# io-a-1.net
KiCad netlist of a schematic drawn in EAGLE
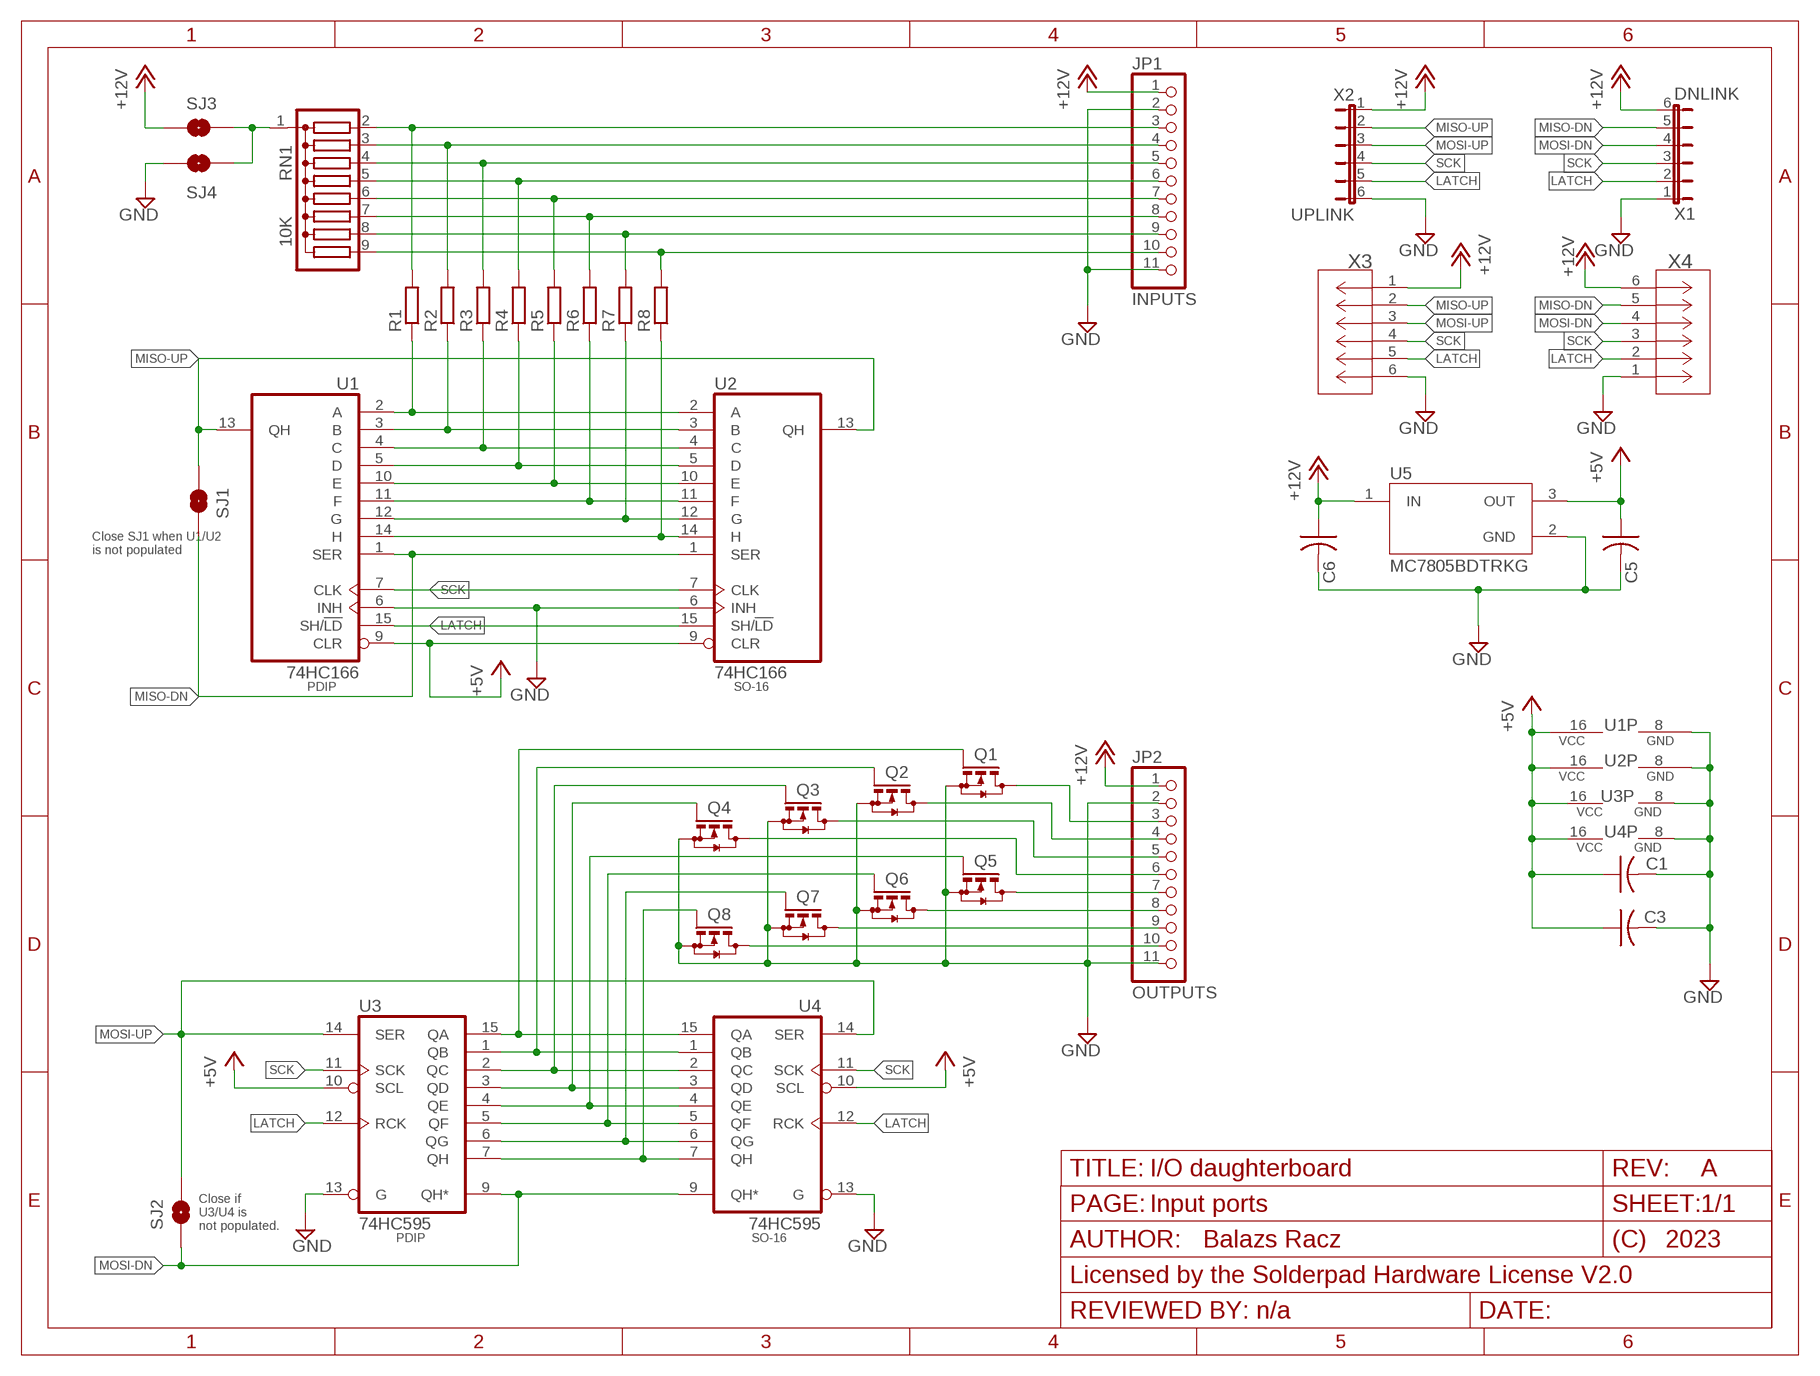
[diagram p0: schematic, sheet 1]

(export (version "E")
  (design (tool "Eeschema 10.0.6"))
  (components
    (comp (ref "C1")
      (value "C-USC0805")
      (footprint "eagle-import:C0805")
      (libsource (lib "eagle-import") (part "C-USC0805"))
    )
    (comp (ref "C3")
      (value "C-USC0805")
      (footprint "eagle-import:C0805")
      (libsource (lib "eagle-import") (part "C-USC0805"))
    )
    (comp (ref "C5")
      (value "C-USC0805")
      (footprint "eagle-import:C0805")
      (libsource (lib "eagle-import") (part "C-USC0805"))
    )
    (comp (ref "C6")
      (value "C-USC0805")
      (footprint "eagle-import:C0805")
      (libsource (lib "eagle-import") (part "C-USC0805"))
    )
    (comp (ref "JP1")
      (value "INPUTS")
      (footprint "eagle-import:1X11")
      (libsource (lib "eagle-import") (part "PINHD-1X11"))
    )
    (comp (ref "JP2")
      (value "OUTPUTS")
      (footprint "eagle-import:1X11")
      (libsource (lib "eagle-import") (part "PINHD-1X11"))
    )
    (comp (ref "Q1")
      (value "BSS123")
      (footprint "eagle-import:SOT23")
      (libsource (lib "eagle-import") (part "BSS123"))
    )
    (comp (ref "Q2")
      (value "BSS123")
      (footprint "eagle-import:SOT23")
      (libsource (lib "eagle-import") (part "BSS123"))
    )
    (comp (ref "Q3")
      (value "BSS123")
      (footprint "eagle-import:SOT23")
      (libsource (lib "eagle-import") (part "BSS123"))
    )
    (comp (ref "Q4")
      (value "BSS123")
      (footprint "eagle-import:SOT23")
      (libsource (lib "eagle-import") (part "BSS123"))
    )
    (comp (ref "Q5")
      (value "BSS123")
      (footprint "eagle-import:SOT23")
      (libsource (lib "eagle-import") (part "BSS123"))
    )
    (comp (ref "Q6")
      (value "BSS123")
      (footprint "eagle-import:SOT23")
      (libsource (lib "eagle-import") (part "BSS123"))
    )
    (comp (ref "Q7")
      (value "BSS123")
      (footprint "eagle-import:SOT23")
      (libsource (lib "eagle-import") (part "BSS123"))
    )
    (comp (ref "Q8")
      (value "BSS123")
      (footprint "eagle-import:SOT23")
      (libsource (lib "eagle-import") (part "BSS123"))
    )
    (comp (ref "R1")
      (value "R-EU_R0805")
      (footprint "eagle-import:R0805")
      (libsource (lib "eagle-import") (part "R-EU_R0805"))
    )
    (comp (ref "R2")
      (value "R-EU_R0805")
      (footprint "eagle-import:R0805")
      (libsource (lib "eagle-import") (part "R-EU_R0805"))
    )
    (comp (ref "R3")
      (value "R-EU_R0805")
      (footprint "eagle-import:R0805")
      (libsource (lib "eagle-import") (part "R-EU_R0805"))
    )
    (comp (ref "R4")
      (value "R-EU_R0805")
      (footprint "eagle-import:R0805")
      (libsource (lib "eagle-import") (part "R-EU_R0805"))
    )
    (comp (ref "R5")
      (value "R-EU_R0805")
      (footprint "eagle-import:R0805")
      (libsource (lib "eagle-import") (part "R-EU_R0805"))
    )
    (comp (ref "R6")
      (value "R-EU_R0805")
      (footprint "eagle-import:R0805")
      (libsource (lib "eagle-import") (part "R-EU_R0805"))
    )
    (comp (ref "R7")
      (value "R-EU_R0805")
      (footprint "eagle-import:R0805")
      (libsource (lib "eagle-import") (part "R-EU_R0805"))
    )
    (comp (ref "R8")
      (value "R-EU_R0805")
      (footprint "eagle-import:R0805")
      (libsource (lib "eagle-import") (part "R-EU_R0805"))
    )
    (comp (ref "RN1")
      (value "10K")
      (footprint "eagle-import:SIL9")
      (libsource (lib "eagle-import") (part "G08R"))
    )
    (comp (ref "SJ1")
      (value "SJRND2")
      (footprint "eagle-import:SJ_RND2")
      (libsource (lib "eagle-import") (part "SJRND2"))
    )
    (comp (ref "SJ2")
      (value "SJRND2")
      (footprint "eagle-import:SJ_RND2")
      (libsource (lib "eagle-import") (part "SJRND2"))
    )
    (comp (ref "SJ3")
      (value "SJRND2")
      (footprint "eagle-import:SJ_RND2")
      (libsource (lib "eagle-import") (part "SJRND2"))
    )
    (comp (ref "SJ4")
      (value "SJRND2")
      (footprint "eagle-import:SJ_RND2")
      (libsource (lib "eagle-import") (part "SJRND2"))
    )
    (comp (ref "U1")
      (value "74HC166")
      (footprint "eagle-import:DIL16")
      (libsource (lib "eagle-import") (part "74166N"))
    )
    (comp (ref "U2")
      (value "74HC166")
      (footprint "eagle-import:SO16")
      (libsource (lib "eagle-import") (part "74166D"))
    )
    (comp (ref "U3")
      (value "74HC595")
      (footprint "eagle-import:DIL16")
      (libsource (lib "eagle-import") (part "74595NHCT"))
    )
    (comp (ref "U4")
      (value "74HC595")
      (footprint "eagle-import:SO16")
      (libsource (lib "eagle-import") (part "74595DHCT"))
    )
    (comp (ref "U5")
      (value "MC7805BDTRKG")
      (footprint "eagle-import:DPAK229P990X238-4N")
      (fields (field (name "MANUFACTURER") "ON Semiconductor"))
      (libsource (lib "eagle-import") (part "MC7805BDTRKG"))
    )
    (comp (ref "X1")
      (value "DNLINK")
      (footprint "eagle-import:JP6F")
      (libsource (lib "eagle-import") (part "JP6-FLAT"))
    )
    (comp (ref "X2")
      (value "UPLINK")
      (footprint "eagle-import:JP6F-FEM")
      (libsource (lib "eagle-import") (part "JP6-FLATFEMALE"))
    )
    (comp (ref "X3")
      (value "MOLEX_530470610CON_530470610_MOL")
      (footprint "eagle-import:CON_530470610_MOL")
      (fields
        (field (name "MANUFACTURER_PART_NUMBER") "530470610")
        (field (name "COPYRIGHT") "Copyright (C) 2023 Ultra Librarian. All rights reserved.")
      )
      (libsource (lib "eagle-import") (part "MOLEX_530470610CON_530470610_MOL"))
    )
    (comp (ref "X4")
      (value "MOLEX_530470610CON_530470610_MOL")
      (footprint "eagle-import:CON_530470610_MOL")
      (fields
        (field (name "MANUFACTURER_PART_NUMBER") "530470610")
        (field (name "COPYRIGHT") "Copyright (C) 2023 Ultra Librarian. All rights reserved.")
      )
      (libsource (lib "eagle-import") (part "MOLEX_530470610CON_530470610_MOL"))
    )
  )
  (nets
    (net (code "1") (name "+5V") (class "Default")
      (node (ref "C1") (pin "1") (pinfunction "1_1") (pintype "passive"))
      (node (ref "C3") (pin "1") (pinfunction "1_1") (pintype "passive"))
      (node (ref "C5") (pin "1") (pinfunction "1_1") (pintype "passive"))
      (node (ref "U1") (pin "16") (pinfunction "VCC_16") (pintype "power_in"))
      (node (ref "U1") (pin "9") (pinfunction "CLR_9") (pintype "input"))
      (node (ref "U2") (pin "16") (pinfunction "VCC_16") (pintype "power_in"))
      (node (ref "U2") (pin "9") (pinfunction "CLR_9") (pintype "input"))
      (node (ref "U3") (pin "10") (pinfunction "SCL_10") (pintype "input"))
      (node (ref "U3") (pin "16") (pinfunction "VCC_16") (pintype "power_in"))
      (node (ref "U4") (pin "10") (pinfunction "SCL_10") (pintype "input"))
      (node (ref "U4") (pin "16") (pinfunction "VCC_16") (pintype "power_in"))
      (node (ref "U5") (pin "3") (pinfunction "OUT_3") (pintype "output"))
    )
    (net (code "2") (name "+12V") (class "Default")
      (node (ref "C6") (pin "1") (pinfunction "1_1") (pintype "passive"))
      (node (ref "JP1") (pin "1") (pinfunction "1_1") (pintype "passive"))
      (node (ref "JP2") (pin "1") (pinfunction "1_1") (pintype "passive"))
      (node (ref "SJ3") (pin "P$2") (pinfunction "2_P$2") (pintype "passive"))
      (node (ref "U5") (pin "1") (pinfunction "IN_1") (pintype "input"))
      (node (ref "X1") (pin "6") (pinfunction "6_6") (pintype "passive"))
      (node (ref "X2") (pin "1") (pinfunction "1_1") (pintype "passive"))
      (node (ref "X3") (pin "1") (pinfunction "1_1") (pintype "passive"))
      (node (ref "X4") (pin "6") (pinfunction "6_6") (pintype "passive"))
    )
    (net (code "3") (name "GND") (class "Default")
      (node (ref "C1") (pin "2") (pinfunction "2_2") (pintype "passive"))
      (node (ref "C3") (pin "2") (pinfunction "2_2") (pintype "passive"))
      (node (ref "C5") (pin "2") (pinfunction "2_2") (pintype "passive"))
      (node (ref "C6") (pin "2") (pinfunction "2_2") (pintype "passive"))
      (node (ref "JP1") (pin "11") (pinfunction "11_11") (pintype "passive"))
      (node (ref "JP1") (pin "2") (pinfunction "2_2") (pintype "passive"))
      (node (ref "JP2") (pin "11") (pinfunction "11_11") (pintype "passive"))
      (node (ref "JP2") (pin "2") (pinfunction "2_2") (pintype "passive"))
      (node (ref "Q1") (pin "2") (pinfunction "S_2") (pintype "passive"))
      (node (ref "Q2") (pin "2") (pinfunction "S_2") (pintype "passive"))
      (node (ref "Q3") (pin "2") (pinfunction "S_2") (pintype "passive"))
      (node (ref "Q4") (pin "2") (pinfunction "S_2") (pintype "passive"))
      (node (ref "Q5") (pin "2") (pinfunction "S_2") (pintype "passive"))
      (node (ref "Q6") (pin "2") (pinfunction "S_2") (pintype "passive"))
      (node (ref "Q7") (pin "2") (pinfunction "S_2") (pintype "passive"))
      (node (ref "Q8") (pin "2") (pinfunction "S_2") (pintype "passive"))
      (node (ref "SJ4") (pin "P$2") (pinfunction "2_P$2") (pintype "passive"))
      (node (ref "U1") (pin "6") (pinfunction "INH_6") (pintype "input"))
      (node (ref "U1") (pin "8") (pinfunction "GND_8") (pintype "power_in"))
      (node (ref "U2") (pin "6") (pinfunction "INH_6") (pintype "input"))
      (node (ref "U2") (pin "8") (pinfunction "GND_8") (pintype "power_in"))
      (node (ref "U3") (pin "13") (pinfunction "G_13") (pintype "input"))
      (node (ref "U3") (pin "8") (pinfunction "GND_8") (pintype "power_in"))
      (node (ref "U4") (pin "13") (pinfunction "G_13") (pintype "input"))
      (node (ref "U4") (pin "8") (pinfunction "GND_8") (pintype "power_in"))
      (node (ref "U5") (pin "2") (pinfunction "GND_2") (pintype "power_in"))
      (node (ref "X1") (pin "1") (pinfunction "1_1") (pintype "passive"))
      (node (ref "X2") (pin "6") (pinfunction "6_6") (pintype "passive"))
      (node (ref "X3") (pin "6") (pinfunction "6_6") (pintype "passive"))
      (node (ref "X4") (pin "1") (pinfunction "1_1") (pintype "passive"))
    )
    (net (code "4") (name "LATCH") (class "Default")
      (node (ref "U1") (pin "15") (pinfunction "SH/~{LD}_15") (pintype "input"))
      (node (ref "U2") (pin "15") (pinfunction "SH/~{LD}_15") (pintype "input"))
      (node (ref "U3") (pin "12") (pinfunction "RCK_12") (pintype "input"))
      (node (ref "U4") (pin "12") (pinfunction "RCK_12") (pintype "input"))
      (node (ref "X1") (pin "2") (pinfunction "2_2") (pintype "passive"))
      (node (ref "X2") (pin "5") (pinfunction "5_5") (pintype "passive"))
      (node (ref "X3") (pin "5") (pinfunction "5_5") (pintype "passive"))
      (node (ref "X4") (pin "2") (pinfunction "2_2") (pintype "passive"))
    )
    (net (code "5") (name "MISO-DN") (class "Default")
      (node (ref "SJ1") (pin "P$1") (pinfunction "1_P$1") (pintype "passive"))
      (node (ref "U1") (pin "1") (pinfunction "SER_1") (pintype "input"))
      (node (ref "U2") (pin "1") (pinfunction "SER_1") (pintype "input"))
      (node (ref "X1") (pin "5") (pinfunction "5_5") (pintype "passive"))
      (node (ref "X4") (pin "5") (pinfunction "5_5") (pintype "passive"))
    )
    (net (code "6") (name "MISO-UP") (class "Default")
      (node (ref "SJ1") (pin "P$2") (pinfunction "2_P$2") (pintype "passive"))
      (node (ref "U1") (pin "13") (pinfunction "QH_13") (pintype "output"))
      (node (ref "U2") (pin "13") (pinfunction "QH_13") (pintype "output"))
      (node (ref "X2") (pin "2") (pinfunction "2_2") (pintype "passive"))
      (node (ref "X3") (pin "2") (pinfunction "2_2") (pintype "passive"))
    )
    (net (code "7") (name "MOSI-DN") (class "Default")
      (node (ref "SJ2") (pin "P$1") (pinfunction "1_P$1") (pintype "passive"))
      (node (ref "U3") (pin "9") (pinfunction "QH*_9") (pintype "tri_state"))
      (node (ref "U4") (pin "9") (pinfunction "QH*_9") (pintype "tri_state"))
      (node (ref "X1") (pin "4") (pinfunction "4_4") (pintype "passive"))
      (node (ref "X4") (pin "4") (pinfunction "4_4") (pintype "passive"))
    )
    (net (code "8") (name "MOSI-UP") (class "Default")
      (node (ref "SJ2") (pin "P$2") (pinfunction "2_P$2") (pintype "passive"))
      (node (ref "U3") (pin "14") (pinfunction "SER_14") (pintype "input"))
      (node (ref "U4") (pin "14") (pinfunction "SER_14") (pintype "input"))
      (node (ref "X2") (pin "3") (pinfunction "3_3") (pintype "passive"))
      (node (ref "X3") (pin "3") (pinfunction "3_3") (pintype "passive"))
    )
    (net (code "9") (name "Net-(JP1-Pad3)") (class "Default")
      (node (ref "JP1") (pin "3") (pinfunction "3_3") (pintype "passive"))
      (node (ref "R1") (pin "2") (pinfunction "2_2") (pintype "passive"))
      (node (ref "RN1") (pin "2") (pinfunction "2_2") (pintype "passive"))
    )
    (net (code "10") (name "Net-(JP1-Pad4)") (class "Default")
      (node (ref "JP1") (pin "4") (pinfunction "4_4") (pintype "passive"))
      (node (ref "R2") (pin "2") (pinfunction "2_2") (pintype "passive"))
      (node (ref "RN1") (pin "3") (pinfunction "3_3") (pintype "passive"))
    )
    (net (code "11") (name "Net-(JP1-Pad5)") (class "Default")
      (node (ref "JP1") (pin "5") (pinfunction "5_5") (pintype "passive"))
      (node (ref "R3") (pin "2") (pinfunction "2_2") (pintype "passive"))
      (node (ref "RN1") (pin "4") (pinfunction "4_4") (pintype "passive"))
    )
    (net (code "12") (name "Net-(JP1-Pad6)") (class "Default")
      (node (ref "JP1") (pin "6") (pinfunction "6_6") (pintype "passive"))
      (node (ref "R4") (pin "2") (pinfunction "2_2") (pintype "passive"))
      (node (ref "RN1") (pin "5") (pinfunction "5_5") (pintype "passive"))
    )
    (net (code "13") (name "Net-(JP1-Pad7)") (class "Default")
      (node (ref "JP1") (pin "7") (pinfunction "7_7") (pintype "passive"))
      (node (ref "R5") (pin "2") (pinfunction "2_2") (pintype "passive"))
      (node (ref "RN1") (pin "6") (pinfunction "6_6") (pintype "passive"))
    )
    (net (code "14") (name "Net-(JP1-Pad8)") (class "Default")
      (node (ref "JP1") (pin "8") (pinfunction "8_8") (pintype "passive"))
      (node (ref "R6") (pin "2") (pinfunction "2_2") (pintype "passive"))
      (node (ref "RN1") (pin "7") (pinfunction "7_7") (pintype "passive"))
    )
    (net (code "15") (name "Net-(JP1-Pad9)") (class "Default")
      (node (ref "JP1") (pin "9") (pinfunction "9_9") (pintype "passive"))
      (node (ref "R7") (pin "2") (pinfunction "2_2") (pintype "passive"))
      (node (ref "RN1") (pin "8") (pinfunction "8_8") (pintype "passive"))
    )
    (net (code "16") (name "Net-(JP1-Pad10)") (class "Default")
      (node (ref "JP1") (pin "10") (pinfunction "10_10") (pintype "passive"))
      (node (ref "R8") (pin "2") (pinfunction "2_2") (pintype "passive"))
      (node (ref "RN1") (pin "9") (pinfunction "9_9") (pintype "passive"))
    )
    (net (code "17") (name "Net-(Q1-D)") (class "Default")
      (node (ref "JP2") (pin "3") (pinfunction "3_3") (pintype "passive"))
      (node (ref "Q1") (pin "3") (pinfunction "D_3") (pintype "passive"))
    )
    (net (code "18") (name "Net-(Q1-G)") (class "Default")
      (node (ref "Q1") (pin "1") (pinfunction "G_1") (pintype "passive"))
      (node (ref "U3") (pin "15") (pinfunction "QA_15") (pintype "tri_state"))
      (node (ref "U4") (pin "15") (pinfunction "QA_15") (pintype "tri_state"))
    )
    (net (code "19") (name "Net-(Q2-D)") (class "Default")
      (node (ref "JP2") (pin "4") (pinfunction "4_4") (pintype "passive"))
      (node (ref "Q2") (pin "3") (pinfunction "D_3") (pintype "passive"))
    )
    (net (code "20") (name "Net-(Q2-G)") (class "Default")
      (node (ref "Q2") (pin "1") (pinfunction "G_1") (pintype "passive"))
      (node (ref "U3") (pin "1") (pinfunction "QB_1") (pintype "tri_state"))
      (node (ref "U4") (pin "1") (pinfunction "QB_1") (pintype "tri_state"))
    )
    (net (code "21") (name "Net-(Q3-D)") (class "Default")
      (node (ref "JP2") (pin "5") (pinfunction "5_5") (pintype "passive"))
      (node (ref "Q3") (pin "3") (pinfunction "D_3") (pintype "passive"))
    )
    (net (code "22") (name "Net-(Q3-G)") (class "Default")
      (node (ref "Q3") (pin "1") (pinfunction "G_1") (pintype "passive"))
      (node (ref "U3") (pin "2") (pinfunction "QC_2") (pintype "tri_state"))
      (node (ref "U4") (pin "2") (pinfunction "QC_2") (pintype "tri_state"))
    )
    (net (code "23") (name "Net-(Q4-D)") (class "Default")
      (node (ref "JP2") (pin "6") (pinfunction "6_6") (pintype "passive"))
      (node (ref "Q4") (pin "3") (pinfunction "D_3") (pintype "passive"))
    )
    (net (code "24") (name "Net-(Q4-G)") (class "Default")
      (node (ref "Q4") (pin "1") (pinfunction "G_1") (pintype "passive"))
      (node (ref "U3") (pin "3") (pinfunction "QD_3") (pintype "tri_state"))
      (node (ref "U4") (pin "3") (pinfunction "QD_3") (pintype "tri_state"))
    )
    (net (code "25") (name "Net-(Q5-D)") (class "Default")
      (node (ref "JP2") (pin "7") (pinfunction "7_7") (pintype "passive"))
      (node (ref "Q5") (pin "3") (pinfunction "D_3") (pintype "passive"))
    )
    (net (code "26") (name "Net-(Q5-G)") (class "Default")
      (node (ref "Q5") (pin "1") (pinfunction "G_1") (pintype "passive"))
      (node (ref "U3") (pin "4") (pinfunction "QE_4") (pintype "tri_state"))
      (node (ref "U4") (pin "4") (pinfunction "QE_4") (pintype "tri_state"))
    )
    (net (code "27") (name "Net-(Q6-D)") (class "Default")
      (node (ref "JP2") (pin "8") (pinfunction "8_8") (pintype "passive"))
      (node (ref "Q6") (pin "3") (pinfunction "D_3") (pintype "passive"))
    )
    (net (code "28") (name "Net-(Q6-G)") (class "Default")
      (node (ref "Q6") (pin "1") (pinfunction "G_1") (pintype "passive"))
      (node (ref "U3") (pin "5") (pinfunction "QF_5") (pintype "tri_state"))
      (node (ref "U4") (pin "5") (pinfunction "QF_5") (pintype "tri_state"))
    )
    (net (code "29") (name "Net-(Q7-D)") (class "Default")
      (node (ref "JP2") (pin "9") (pinfunction "9_9") (pintype "passive"))
      (node (ref "Q7") (pin "3") (pinfunction "D_3") (pintype "passive"))
    )
    (net (code "30") (name "Net-(Q7-G)") (class "Default")
      (node (ref "Q7") (pin "1") (pinfunction "G_1") (pintype "passive"))
      (node (ref "U3") (pin "6") (pinfunction "QG_6") (pintype "tri_state"))
      (node (ref "U4") (pin "6") (pinfunction "QG_6") (pintype "tri_state"))
    )
    (net (code "31") (name "Net-(Q8-D)") (class "Default")
      (node (ref "JP2") (pin "10") (pinfunction "10_10") (pintype "passive"))
      (node (ref "Q8") (pin "3") (pinfunction "D_3") (pintype "passive"))
    )
    (net (code "32") (name "Net-(Q8-G)") (class "Default")
      (node (ref "Q8") (pin "1") (pinfunction "G_1") (pintype "passive"))
      (node (ref "U3") (pin "7") (pinfunction "QH_7") (pintype "tri_state"))
      (node (ref "U4") (pin "7") (pinfunction "QH_7") (pintype "tri_state"))
    )
    (net (code "33") (name "Net-(SJ3-1)") (class "Default")
      (node (ref "RN1") (pin "1") (pinfunction "1_1") (pintype "passive"))
      (node (ref "SJ3") (pin "P$1") (pinfunction "1_P$1") (pintype "passive"))
      (node (ref "SJ4") (pin "P$1") (pinfunction "1_P$1") (pintype "passive"))
    )
    (net (code "34") (name "Net-(U1A-A)") (class "Default")
      (node (ref "R1") (pin "1") (pinfunction "1_1") (pintype "passive"))
      (node (ref "U1") (pin "2") (pinfunction "A_2") (pintype "input"))
      (node (ref "U2") (pin "2") (pinfunction "A_2") (pintype "input"))
    )
    (net (code "35") (name "Net-(U1A-B)") (class "Default")
      (node (ref "R2") (pin "1") (pinfunction "1_1") (pintype "passive"))
      (node (ref "U1") (pin "3") (pinfunction "B_3") (pintype "input"))
      (node (ref "U2") (pin "3") (pinfunction "B_3") (pintype "input"))
    )
    (net (code "36") (name "Net-(U1A-C)") (class "Default")
      (node (ref "R3") (pin "1") (pinfunction "1_1") (pintype "passive"))
      (node (ref "U1") (pin "4") (pinfunction "C_4") (pintype "input"))
      (node (ref "U2") (pin "4") (pinfunction "C_4") (pintype "input"))
    )
    (net (code "37") (name "Net-(U1A-D)") (class "Default")
      (node (ref "R4") (pin "1") (pinfunction "1_1") (pintype "passive"))
      (node (ref "U1") (pin "5") (pinfunction "D_5") (pintype "input"))
      (node (ref "U2") (pin "5") (pinfunction "D_5") (pintype "input"))
    )
    (net (code "38") (name "Net-(U1A-E)") (class "Default")
      (node (ref "R5") (pin "1") (pinfunction "1_1") (pintype "passive"))
      (node (ref "U1") (pin "10") (pinfunction "E_10") (pintype "input"))
      (node (ref "U2") (pin "10") (pinfunction "E_10") (pintype "input"))
    )
    (net (code "39") (name "Net-(U1A-F)") (class "Default")
      (node (ref "R6") (pin "1") (pinfunction "1_1") (pintype "passive"))
      (node (ref "U1") (pin "11") (pinfunction "F_11") (pintype "input"))
      (node (ref "U2") (pin "11") (pinfunction "F_11") (pintype "input"))
    )
    (net (code "40") (name "Net-(U1A-G)") (class "Default")
      (node (ref "R7") (pin "1") (pinfunction "1_1") (pintype "passive"))
      (node (ref "U1") (pin "12") (pinfunction "G_12") (pintype "input"))
      (node (ref "U2") (pin "12") (pinfunction "G_12") (pintype "input"))
    )
    (net (code "41") (name "Net-(U1A-H)") (class "Default")
      (node (ref "R8") (pin "1") (pinfunction "1_1") (pintype "passive"))
      (node (ref "U1") (pin "14") (pinfunction "H_14") (pintype "input"))
      (node (ref "U2") (pin "14") (pinfunction "H_14") (pintype "input"))
    )
    (net (code "42") (name "SCK") (class "Default")
      (node (ref "U1") (pin "7") (pinfunction "CLK_7") (pintype "input"))
      (node (ref "U2") (pin "7") (pinfunction "CLK_7") (pintype "input"))
      (node (ref "U3") (pin "11") (pinfunction "SCK_11") (pintype "input"))
      (node (ref "U4") (pin "11") (pinfunction "SCK_11") (pintype "input"))
      (node (ref "X1") (pin "3") (pinfunction "3_3") (pintype "passive"))
      (node (ref "X2") (pin "4") (pinfunction "4_4") (pintype "passive"))
      (node (ref "X3") (pin "4") (pinfunction "4_4") (pintype "passive"))
      (node (ref "X4") (pin "3") (pinfunction "3_3") (pintype "passive"))
    )
  )
)
